# Un_Battery_V2_0.net
KiCad netlist of a schematic drawn in EAGLE
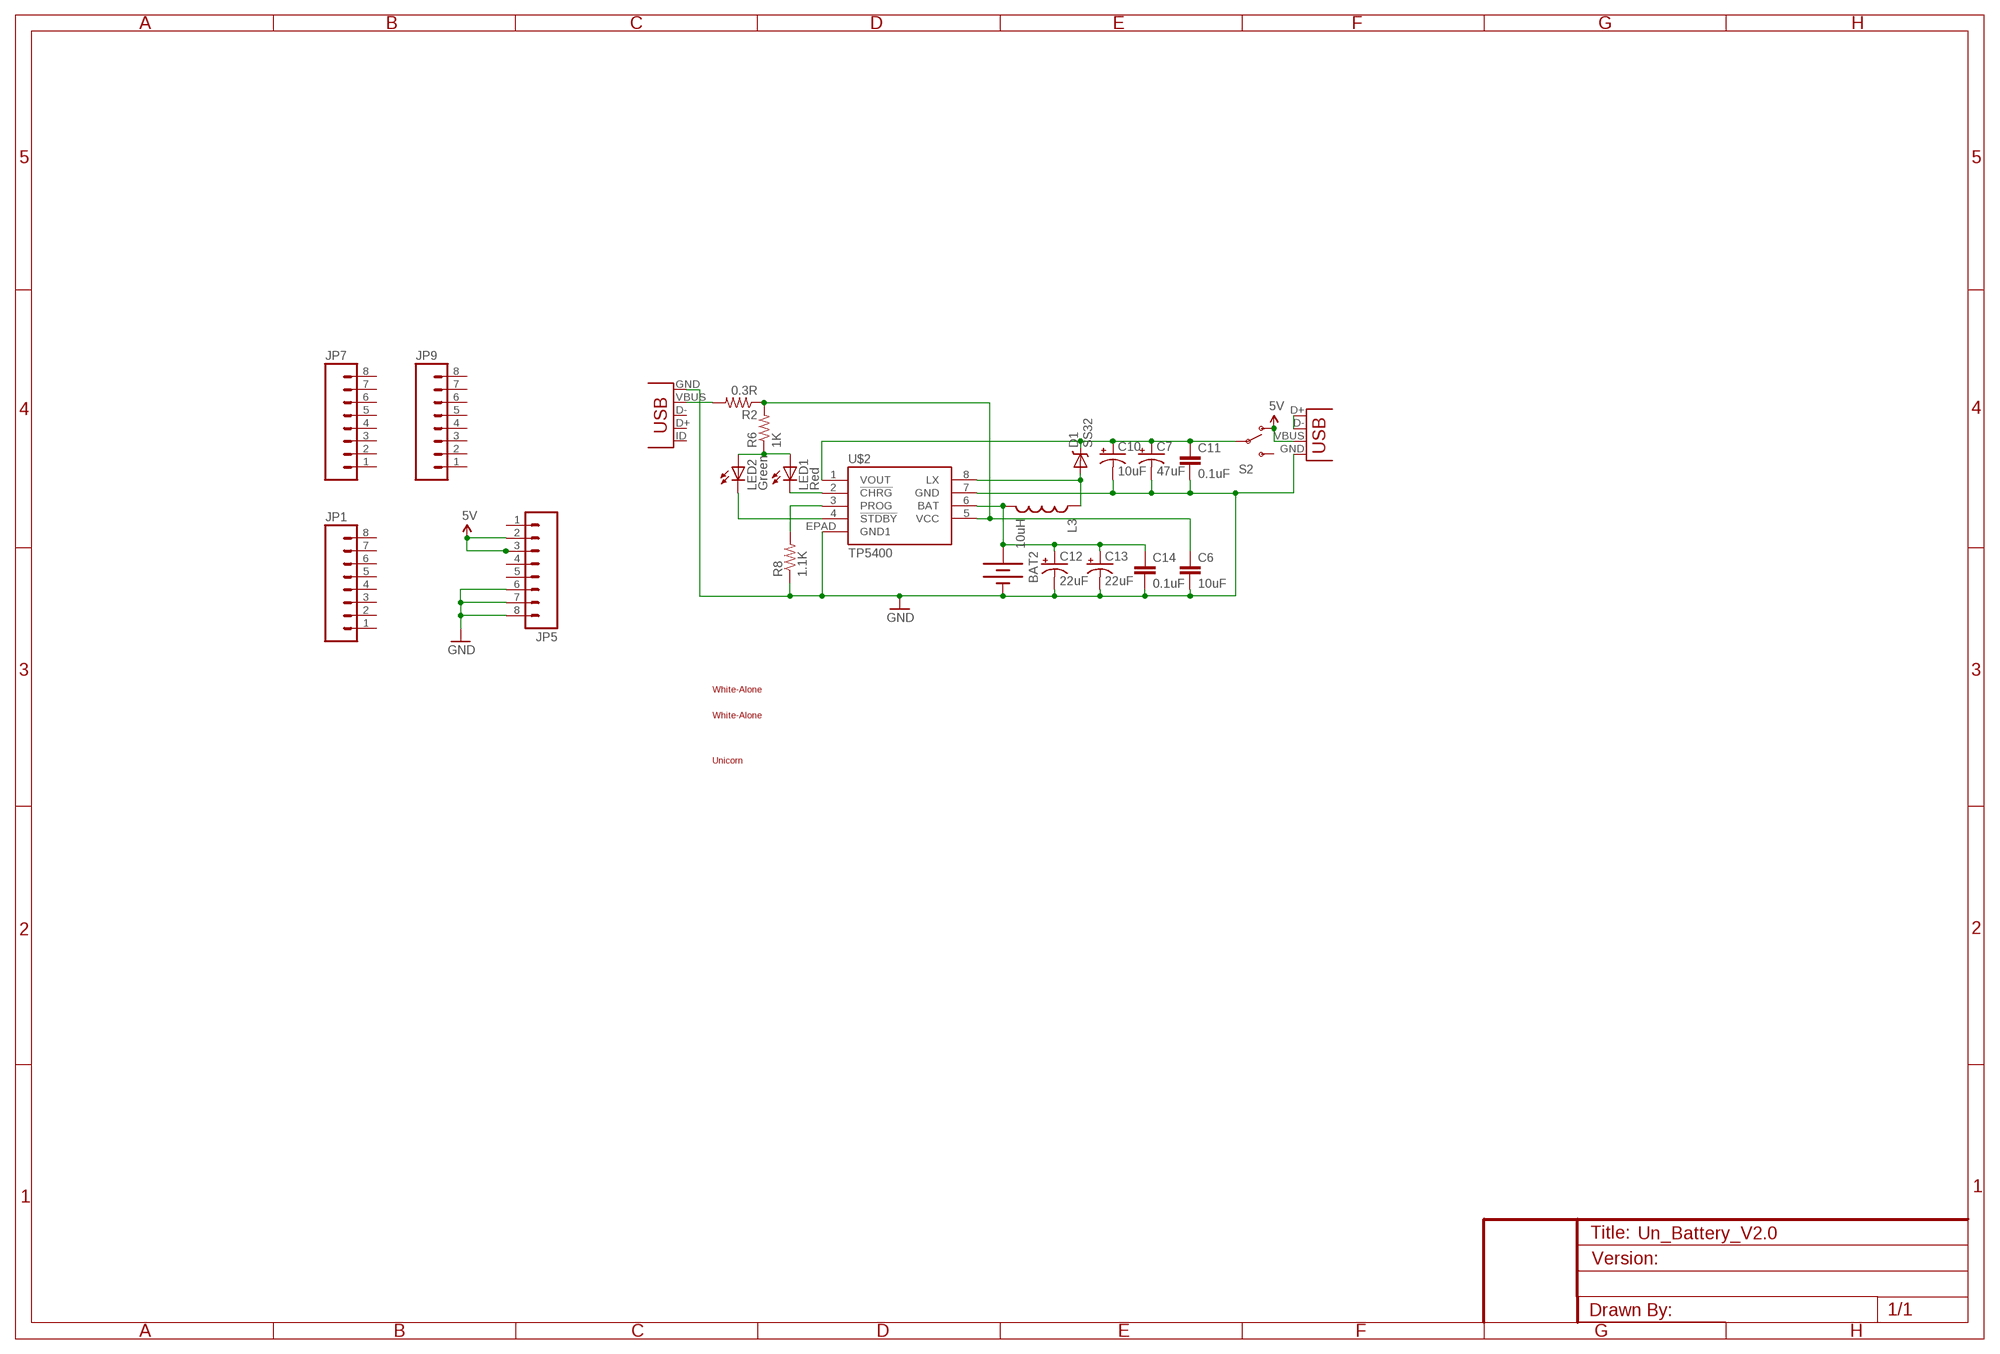
[diagram p0: schematic, sheet 1]

(export (version "E")
  (design (tool "Eeschema 10.0.6"))
  (components
    (comp (ref "BAT2")
      (value "BATTERYLIPO")
      (footprint "eagle-import:BATTERY-LIPO")
      (libsource (lib "eagle-import") (part "BATTERYLIPO"))
    )
    (comp (ref "C6")
      (value "10uF")
      (footprint "eagle-import:1206")
      (libsource (lib "eagle-import") (part "CAP1206"))
    )
    (comp (ref "C7")
      (value "47uF")
      (footprint "eagle-import:PANASONIC_D")
      (libsource (lib "eagle-import") (part "CAP_POLD"))
    )
    (comp (ref "C10")
      (value "10uF")
      (footprint "eagle-import:EIA3216")
      (libsource (lib "eagle-import") (part "CAP_POL1206"))
    )
    (comp (ref "C11")
      (value "0.1uF")
      (footprint "eagle-import:1206")
      (libsource (lib "eagle-import") (part "CAP1206"))
    )
    (comp (ref "C12")
      (value "22uF")
      (footprint "eagle-import:EIA3216")
      (libsource (lib "eagle-import") (part "CAP_POL1206"))
    )
    (comp (ref "C13")
      (value "22uF")
      (footprint "eagle-import:EIA3216")
      (libsource (lib "eagle-import") (part "CAP_POL1206"))
    )
    (comp (ref "C14")
      (value "0.1uF")
      (footprint "eagle-import:1206")
      (libsource (lib "eagle-import") (part "CAP1206"))
    )
    (comp (ref "D1")
      (value "SS32")
      (footprint "eagle-import:SMA-DIODE")
      (libsource (lib "eagle-import") (part "DIODE-SCHOTTKY_"))
    )
    (comp (ref "JP1")
      (value "M081X08")
      (footprint "eagle-import:1X08")
      (libsource (lib "eagle-import") (part "M081X08"))
    )
    (comp (ref "JP5")
      (value "M081X08")
      (footprint "eagle-import:1X08")
      (libsource (lib "eagle-import") (part "M081X08"))
    )
    (comp (ref "JP7")
      (value "M081X08")
      (footprint "eagle-import:1X08")
      (libsource (lib "eagle-import") (part "M081X08"))
    )
    (comp (ref "JP9")
      (value "M081X08")
      (footprint "eagle-import:1X08")
      (libsource (lib "eagle-import") (part "M081X08"))
    )
    (comp (ref "L3")
      (value "10uH")
      (footprint "eagle-import:CR75")
      (libsource (lib "eagle-import") (part "INDUCTORCR75"))
    )
    (comp (ref "LED1")
      (value "Red")
      (footprint "eagle-import:LED-0805")
      (libsource (lib "eagle-import") (part "LED0805"))
    )
    (comp (ref "LED2")
      (value "Green")
      (footprint "eagle-import:LED-0805")
      (libsource (lib "eagle-import") (part "LED0805"))
    )
    (comp (ref "R2")
      (value "0.3R")
      (footprint "eagle-import:1206")
      (libsource (lib "eagle-import") (part "RESISTOR1206"))
    )
    (comp (ref "R6")
      (value "1K")
      (footprint "eagle-import:0805")
      (libsource (lib "eagle-import") (part "RESISTOR0805-RES"))
    )
    (comp (ref "R8")
      (value "1.1K")
      (footprint "eagle-import:0805")
      (libsource (lib "eagle-import") (part "RESISTOR0805-RES"))
    )
    (comp (ref "S2")
      (value "SWITCH-SPST")
      (footprint "eagle-import:SWITCH-SPDT2")
      (libsource (lib "eagle-import") (part "SWITCH-SPST"))
    )
    (comp (ref "U$2")
      (value "TP5400")
      (footprint "eagle-import:SO08-EPAD")
      (libsource (lib "eagle-import") (part "TP5400"))
    )
    (comp (ref "U$4")
      (value "WHITE-ALONE_2")
      (footprint "eagle-import:WHITE-ALONE_2")
      (libsource (lib "eagle-import") (part "WHITE-ALONE_2"))
    )
    (comp (ref "U$5")
      (value "WHITE-ALONE_2")
      (footprint "eagle-import:WHITE-ALONE_2")
      (libsource (lib "eagle-import") (part "WHITE-ALONE_2"))
    )
    (comp (ref "U$6")
      (value "USB_5-SMD")
      (footprint "eagle-import:USB-MINIB")
      (libsource (lib "eagle-import") (part "USB_5-SMD"))
    )
    (comp (ref "U$7")
      (value "UNICORN_1")
      (footprint "eagle-import:UNICORN_1")
      (libsource (lib "eagle-import") (part "UNICORN_1"))
    )
    (comp (ref "X2")
      (value "USB-A-S")
      (footprint "eagle-import:USB-A-S")
      (libsource (lib "eagle-import") (part "USB-A-S"))
    )
  )
  (nets
    (net (code "1") (name "5V") (class "Default")
      (node (ref "JP5") (pin "2") (pinfunction "2_2") (pintype "passive"))
      (node (ref "JP5") (pin "3") (pinfunction "3_3") (pintype "passive"))
      (node (ref "S2") (pin "1") (pinfunction "O_1") (pintype "passive"))
      (node (ref "X2") (pin "VBUS") (pinfunction "VBUS_VBUS") (pintype "bidirectional"))
    )
    (net (code "2") (name "GND") (class "Default")
      (node (ref "BAT2") (pin "-") (pinfunction "-_-") (pintype "power_in"))
      (node (ref "C10") (pin "C") (pinfunction "-_C") (pintype "passive"))
      (node (ref "C11") (pin "2") (pinfunction "2_2") (pintype "passive"))
      (node (ref "C12") (pin "C") (pinfunction "-_C") (pintype "passive"))
      (node (ref "C13") (pin "C") (pinfunction "-_C") (pintype "passive"))
      (node (ref "C14") (pin "2") (pinfunction "2_2") (pintype "passive"))
      (node (ref "C6") (pin "2") (pinfunction "2_2") (pintype "passive"))
      (node (ref "C7") (pin "-") (pinfunction "-_-") (pintype "passive"))
      (node (ref "JP5") (pin "6") (pinfunction "6_6") (pintype "passive"))
      (node (ref "JP5") (pin "7") (pinfunction "7_7") (pintype "passive"))
      (node (ref "JP5") (pin "8") (pinfunction "8_8") (pintype "passive"))
      (node (ref "R8") (pin "1") (pinfunction "1_1") (pintype "passive"))
      (node (ref "U$2") (pin "7") (pinfunction "GND_7") (pintype "bidirectional"))
      (node (ref "U$2") (pin "EPAD") (pinfunction "GND1_EPAD") (pintype "power_in"))
      (node (ref "U$6") (pin "GND") (pinfunction "GND_GND") (pintype "bidirectional"))
      (node (ref "X2") (pin "GND") (pinfunction "GND_GND") (pintype "bidirectional"))
    )
    (net (code "3") (name "Net-(C10-+)") (class "Default")
      (node (ref "C10") (pin "A") (pinfunction "+_A") (pintype "passive"))
      (node (ref "C11") (pin "1") (pinfunction "1_1") (pintype "passive"))
      (node (ref "C7") (pin "+") (pinfunction "+_+") (pintype "passive"))
      (node (ref "D1") (pin "C") (pinfunction "C_C") (pintype "passive"))
      (node (ref "S2") (pin "2") (pinfunction "P_2") (pintype "passive"))
      (node (ref "U$2") (pin "1") (pinfunction "VOUT_1") (pintype "bidirectional"))
    )
    (net (code "4") (name "Net-(C12-+)") (class "Default")
      (node (ref "BAT2") (pin "+") (pinfunction "+_+") (pintype "power_in"))
      (node (ref "C12") (pin "A") (pinfunction "+_A") (pintype "passive"))
      (node (ref "C13") (pin "A") (pinfunction "+_A") (pintype "passive"))
      (node (ref "C14") (pin "1") (pinfunction "1_1") (pintype "passive"))
      (node (ref "L3") (pin "P$2") (pinfunction "2_P$2") (pintype "passive"))
      (node (ref "U$2") (pin "6") (pinfunction "BAT_6") (pintype "bidirectional"))
    )
    (net (code "5") (name "Net-(L3-1)") (class "Default")
      (node (ref "D1") (pin "A") (pinfunction "A_A") (pintype "passive"))
      (node (ref "L3") (pin "P$1") (pinfunction "1_P$1") (pintype "passive"))
      (node (ref "U$2") (pin "8") (pinfunction "LX_8") (pintype "power_in"))
    )
    (net (code "6") (name "Net-(LED1-A)") (class "Default")
      (node (ref "LED1") (pin "1") (pinfunction "A_1") (pintype "passive"))
      (node (ref "LED2") (pin "1") (pinfunction "A_1") (pintype "passive"))
      (node (ref "R6") (pin "1") (pinfunction "1_1") (pintype "passive"))
    )
    (net (code "7") (name "Net-(LED1-C)") (class "Default")
      (node (ref "LED1") (pin "2") (pinfunction "C_2") (pintype "passive"))
      (node (ref "U$2") (pin "2") (pinfunction "~{CHRG}_2") (pintype "bidirectional"))
    )
    (net (code "8") (name "Net-(LED2-C)") (class "Default")
      (node (ref "LED2") (pin "2") (pinfunction "C_2") (pintype "passive"))
      (node (ref "U$2") (pin "4") (pinfunction "~{STDBY}_4") (pintype "power_in"))
    )
    (net (code "9") (name "Net-(R2-Pad2)") (class "Default")
      (node (ref "R2") (pin "2") (pinfunction "2_2") (pintype "passive"))
      (node (ref "U$6") (pin "VBUS") (pinfunction "VBUS_VBUS") (pintype "bidirectional"))
    )
    (net (code "10") (name "Net-(U$2-PROG)") (class "Default")
      (node (ref "R8") (pin "2") (pinfunction "2_2") (pintype "passive"))
      (node (ref "U$2") (pin "3") (pinfunction "PROG_3") (pintype "bidirectional"))
    )
    (net (code "11") (name "Net-(U$2-VCC)") (class "Default")
      (node (ref "C6") (pin "1") (pinfunction "1_1") (pintype "passive"))
      (node (ref "R2") (pin "1") (pinfunction "1_1") (pintype "passive"))
      (node (ref "R6") (pin "2") (pinfunction "2_2") (pintype "passive"))
      (node (ref "U$2") (pin "5") (pinfunction "VCC_5") (pintype "bidirectional"))
    )
    (net (code "12") (name "Net-(X2-PadD+)") (class "Default")
      (node (ref "X2") (pin "D+") (pinfunction "D+_D+") (pintype "bidirectional"))
      (node (ref "X2") (pin "D-") (pinfunction "D-_D-") (pintype "bidirectional"))
    )
    (net (code "13") (name "unconnected-(JP1-Pad1)") (class "Default")
      (node (ref "JP1") (pin "1") (pinfunction "1_1") (pintype "passive"))
    )
    (net (code "14") (name "unconnected-(JP1-Pad2)") (class "Default")
      (node (ref "JP1") (pin "2") (pinfunction "2_2") (pintype "passive"))
    )
    (net (code "15") (name "unconnected-(JP1-Pad3)") (class "Default")
      (node (ref "JP1") (pin "3") (pinfunction "3_3") (pintype "passive"))
    )
    (net (code "16") (name "unconnected-(JP1-Pad4)") (class "Default")
      (node (ref "JP1") (pin "4") (pinfunction "4_4") (pintype "passive"))
    )
    (net (code "17") (name "unconnected-(JP1-Pad5)") (class "Default")
      (node (ref "JP1") (pin "5") (pinfunction "5_5") (pintype "passive"))
    )
    (net (code "18") (name "unconnected-(JP1-Pad6)") (class "Default")
      (node (ref "JP1") (pin "6") (pinfunction "6_6") (pintype "passive"))
    )
    (net (code "19") (name "unconnected-(JP1-Pad7)") (class "Default")
      (node (ref "JP1") (pin "7") (pinfunction "7_7") (pintype "passive"))
    )
    (net (code "20") (name "unconnected-(JP1-Pad8)") (class "Default")
      (node (ref "JP1") (pin "8") (pinfunction "8_8") (pintype "passive"))
    )
    (net (code "21") (name "unconnected-(JP5-Pad1)") (class "Default")
      (node (ref "JP5") (pin "1") (pinfunction "1_1") (pintype "passive"))
    )
    (net (code "22") (name "unconnected-(JP5-Pad4)") (class "Default")
      (node (ref "JP5") (pin "4") (pinfunction "4_4") (pintype "passive"))
    )
    (net (code "23") (name "unconnected-(JP5-Pad5)") (class "Default")
      (node (ref "JP5") (pin "5") (pinfunction "5_5") (pintype "passive"))
    )
    (net (code "24") (name "unconnected-(JP7-Pad1)") (class "Default")
      (node (ref "JP7") (pin "1") (pinfunction "1_1") (pintype "passive"))
    )
    (net (code "25") (name "unconnected-(JP7-Pad2)") (class "Default")
      (node (ref "JP7") (pin "2") (pinfunction "2_2") (pintype "passive"))
    )
    (net (code "26") (name "unconnected-(JP7-Pad3)") (class "Default")
      (node (ref "JP7") (pin "3") (pinfunction "3_3") (pintype "passive"))
    )
    (net (code "27") (name "unconnected-(JP7-Pad4)") (class "Default")
      (node (ref "JP7") (pin "4") (pinfunction "4_4") (pintype "passive"))
    )
    (net (code "28") (name "unconnected-(JP7-Pad5)") (class "Default")
      (node (ref "JP7") (pin "5") (pinfunction "5_5") (pintype "passive"))
    )
    (net (code "29") (name "unconnected-(JP7-Pad6)") (class "Default")
      (node (ref "JP7") (pin "6") (pinfunction "6_6") (pintype "passive"))
    )
    (net (code "30") (name "unconnected-(JP7-Pad7)") (class "Default")
      (node (ref "JP7") (pin "7") (pinfunction "7_7") (pintype "passive"))
    )
    (net (code "31") (name "unconnected-(JP7-Pad8)") (class "Default")
      (node (ref "JP7") (pin "8") (pinfunction "8_8") (pintype "passive"))
    )
    (net (code "32") (name "unconnected-(JP9-Pad1)") (class "Default")
      (node (ref "JP9") (pin "1") (pinfunction "1_1") (pintype "passive"))
    )
    (net (code "33") (name "unconnected-(JP9-Pad2)") (class "Default")
      (node (ref "JP9") (pin "2") (pinfunction "2_2") (pintype "passive"))
    )
    (net (code "34") (name "unconnected-(JP9-Pad3)") (class "Default")
      (node (ref "JP9") (pin "3") (pinfunction "3_3") (pintype "passive"))
    )
    (net (code "35") (name "unconnected-(JP9-Pad4)") (class "Default")
      (node (ref "JP9") (pin "4") (pinfunction "4_4") (pintype "passive"))
    )
    (net (code "36") (name "unconnected-(JP9-Pad5)") (class "Default")
      (node (ref "JP9") (pin "5") (pinfunction "5_5") (pintype "passive"))
    )
    (net (code "37") (name "unconnected-(JP9-Pad6)") (class "Default")
      (node (ref "JP9") (pin "6") (pinfunction "6_6") (pintype "passive"))
    )
    (net (code "38") (name "unconnected-(JP9-Pad7)") (class "Default")
      (node (ref "JP9") (pin "7") (pinfunction "7_7") (pintype "passive"))
    )
    (net (code "39") (name "unconnected-(JP9-Pad8)") (class "Default")
      (node (ref "JP9") (pin "8") (pinfunction "8_8") (pintype "passive"))
    )
    (net (code "40") (name "unconnected-(S2-S-Pad3)") (class "Default")
      (node (ref "S2") (pin "3") (pinfunction "S_3") (pintype "passive"))
    )
    (net (code "41") (name "unconnected-(U$6-PadD+)") (class "Default")
      (node (ref "U$6") (pin "D+") (pinfunction "D+_D+") (pintype "bidirectional"))
    )
    (net (code "42") (name "unconnected-(U$6-PadD-)") (class "Default")
      (node (ref "U$6") (pin "D-") (pinfunction "D-_D-") (pintype "bidirectional"))
    )
    (net (code "43") (name "unconnected-(U$6-USBID-PadID)") (class "Default")
      (node (ref "U$6") (pin "ID") (pinfunction "USBID_ID") (pintype "bidirectional"))
    )
  )
)
